# PowerMeter_Cpu.net
KiCad netlist of a schematic drawn in Altium Designer
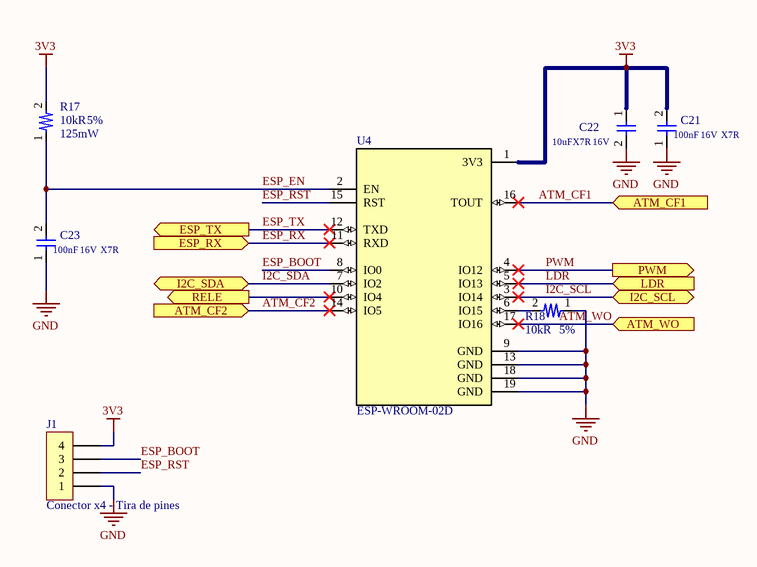
[diagram p0: PowerMeter_Cpu.SchDoc]

(export (version "E")
  (design (tool "Eeschema 10.0.6"))
  (components
    (comp (ref "C21")
      (value "CAP Ceramic  0.1uF 16V X7R")
      (footprint "C_0805")
      (description "Cap Ceramic 0.1uF 16V X7R 10% SMD 0805 125C Paper T/R")
      (fields
        (field (name "MANUFACTURER") "Yageo")
        (field (name "MANUFACTURER PART NUMBER") "CC0805KPX7R7BB104")
        (field (name "CAPACITANCE") "100nF")
        (field (name "VOLTAGE RATING (DC)") "16V")
        (field (name "DIELECTRIC") "X7R")
      )
      (libsource (lib "PowerMeter") (part "CAP_NP"))
    )
    (comp (ref "C22")
      (value "CAP Ceramic  10uF 16V X7R")
      (footprint "C_1206")
      (description "CL31 Series 1206 10 uF 16 V ±10% Tolerance X7R Multilayer Ceramic Capacitor")
      (fields
        (field (name "MANUFACTURER") "Samsung")
        (field (name "MANUFACTURER PART NUMBER") "CL31B106KOHNNNF")
        (field (name "CAPACITANCE") "10uF")
        (field (name "DIELECTRIC") "X7R")
        (field (name "VOLTAGE RATING") "16V")
      )
      (libsource (lib "PowerMeter") (part "CAP_NP"))
    )
    (comp (ref "C23")
      (value "CAP Ceramic  0.1uF 16V X7R")
      (footprint "C_0805")
      (description "Cap Ceramic 0.1uF 16V X7R 10% SMD 0805 125C Paper T/R")
      (fields
        (field (name "MANUFACTURER") "Yageo")
        (field (name "MANUFACTURER PART NUMBER") "CC0805KPX7R7BB104")
        (field (name "CAPACITANCE") "100nF")
        (field (name "VOLTAGE RATING (DC)") "16V")
        (field (name "DIELECTRIC") "X7R")
      )
      (libsource (lib "PowerMeter") (part "CAP_NP"))
    )
    (comp (ref "J1")
      (value "Conector x4 - Tira de pines")
      (footprint "Tira de pinesx4")
      (libsource (lib "PowerMeter") (part "Conector x4"))
    )
    (comp (ref "R17")
      (value "RES 10kOhm 5% 1/8W")
      (footprint "R_0805")
      (description "Res Thick Film 0805 10K Ohm 5% 1/8W ±200ppm/°C Molded SMD SMD Paper T/R")
      (fields
        (field (name "MANUFACTURER") "Vishay Dale")
        (field (name "MANUFACTURER PART NUMBER") "CRCW080510K0JNEB")
        (field (name "RESISTANCE") "10kR")
        (field (name "TOLERANCE") "5%")
        (field (name "POWER RATING") "125mW")
      )
      (libsource (lib "PowerMeter") (part "RES"))
    )
    (comp (ref "R18")
      (value "RES 10kOhm 5% 1/8W")
      (footprint "R_0805")
      (description "Res Thick Film 0805 10K Ohm 5% 1/8W ±200ppm/°C Molded SMD SMD Paper T/R")
      (fields
        (field (name "MANUFACTURER") "Vishay Dale")
        (field (name "MANUFACTURER PART NUMBER") "CRCW080510K0JNEB")
        (field (name "RESISTANCE") "10kR")
        (field (name "TOLERANCE") "5%")
      )
      (libsource (lib "PowerMeter") (part "RES"))
    )
    (comp (ref "U4")
      (value "ESP-WROOM-02D")
      (footprint "ESP-WROOM-02D")
      (description "Wi-Fi Module ESP8266EX SPI 2MB Flash UART w/ Antenna")
      (fields (field (name "MF") "Espressif Systems"))
      (libsource (lib "PowerMeter") (part "ESP-WROOM-02D"))
    )
  )
  (nets
    (net (code "1") (name "/ATM_CF1") (class "Default")
      (node (ref "U4") (pin "16") (pinfunction "TOUT_16") (pintype "bidirectional+no_connect"))
    )
    (net (code "2") (name "/ATM_CF2") (class "Default")
      (node (ref "U4") (pin "14") (pinfunction "IO5_14") (pintype "bidirectional+no_connect"))
    )
    (net (code "3") (name "/ATM_WO") (class "Default")
      (node (ref "U4") (pin "17") (pinfunction "IO16_17") (pintype "bidirectional+no_connect"))
    )
    (net (code "4") (name "/ESP_BOOT") (class "Default")
      (node (ref "J1") (pin "3") (pinfunction "3_3") (pintype "passive"))
      (node (ref "U4") (pin "8") (pinfunction "IO0_8") (pintype "bidirectional"))
    )
    (net (code "5") (name "/ESP_EN") (class "Default")
      (node (ref "C23") (pin "2") (pintype "passive"))
      (node (ref "R17") (pin "1") (pintype "passive"))
      (node (ref "U4") (pin "2") (pinfunction "EN_2") (pintype "passive"))
    )
    (net (code "6") (name "/ESP_RST") (class "Default")
      (node (ref "J1") (pin "2") (pinfunction "2_2") (pintype "passive"))
      (node (ref "U4") (pin "15") (pinfunction "RST_15") (pintype "passive"))
    )
    (net (code "7") (name "/ESP_RX") (class "Default")
      (node (ref "U4") (pin "11") (pinfunction "RXD_11") (pintype "bidirectional+no_connect"))
    )
    (net (code "8") (name "/ESP_TX") (class "Default")
      (node (ref "U4") (pin "12") (pinfunction "TXD_12") (pintype "bidirectional+no_connect"))
    )
    (net (code "9") (name "/I2C_SCL") (class "Default")
      (node (ref "U4") (pin "3") (pinfunction "IO14_3") (pintype "bidirectional+no_connect"))
    )
    (net (code "10") (name "/I2C_SDA") (class "Default")
      (node (ref "U4") (pin "7") (pinfunction "IO2_7") (pintype "bidirectional"))
    )
    (net (code "11") (name "/LDR") (class "Default")
      (node (ref "U4") (pin "5") (pinfunction "IO13_5") (pintype "bidirectional+no_connect"))
    )
    (net (code "12") (name "/PWM") (class "Default")
      (node (ref "U4") (pin "4") (pinfunction "IO12_4") (pintype "bidirectional+no_connect"))
    )
    (net (code "13") (name "/RELE") (class "Default")
      (node (ref "U4") (pin "10") (pinfunction "IO4_10") (pintype "bidirectional+no_connect"))
    )
    (net (code "14") (name "3V3") (class "Default")
      (node (ref "C21") (pin "2") (pintype "passive"))
      (node (ref "C22") (pin "1") (pintype "passive"))
      (node (ref "J1") (pin "4") (pinfunction "4_4") (pintype "passive"))
      (node (ref "R17") (pin "2") (pintype "passive"))
      (node (ref "U4") (pin "1") (pinfunction "3V3_1") (pintype "power_in"))
    )
    (net (code "15") (name "GND") (class "Default")
      (node (ref "C21") (pin "1") (pintype "passive"))
      (node (ref "C22") (pin "2") (pintype "passive"))
      (node (ref "C23") (pin "1") (pintype "passive"))
      (node (ref "J1") (pin "1") (pinfunction "1_1") (pintype "passive"))
      (node (ref "R18") (pin "1") (pintype "passive"))
      (node (ref "U4") (pin "13") (pinfunction "GND_13") (pintype "power_in"))
      (node (ref "U4") (pin "18") (pinfunction "GND_18") (pintype "power_in"))
      (node (ref "U4") (pin "19") (pinfunction "GND_19") (pintype "power_in"))
      (node (ref "U4") (pin "9") (pinfunction "GND_9") (pintype "power_in"))
    )
    (net (code "16") (name "Net-(U4-IO15)") (class "Default")
      (node (ref "R18") (pin "2") (pintype "passive"))
      (node (ref "U4") (pin "6") (pinfunction "IO15_6") (pintype "bidirectional"))
    )
  )
)
